# Level_Shifters.net
KiCad netlist of a schematic drawn in Altium Designer
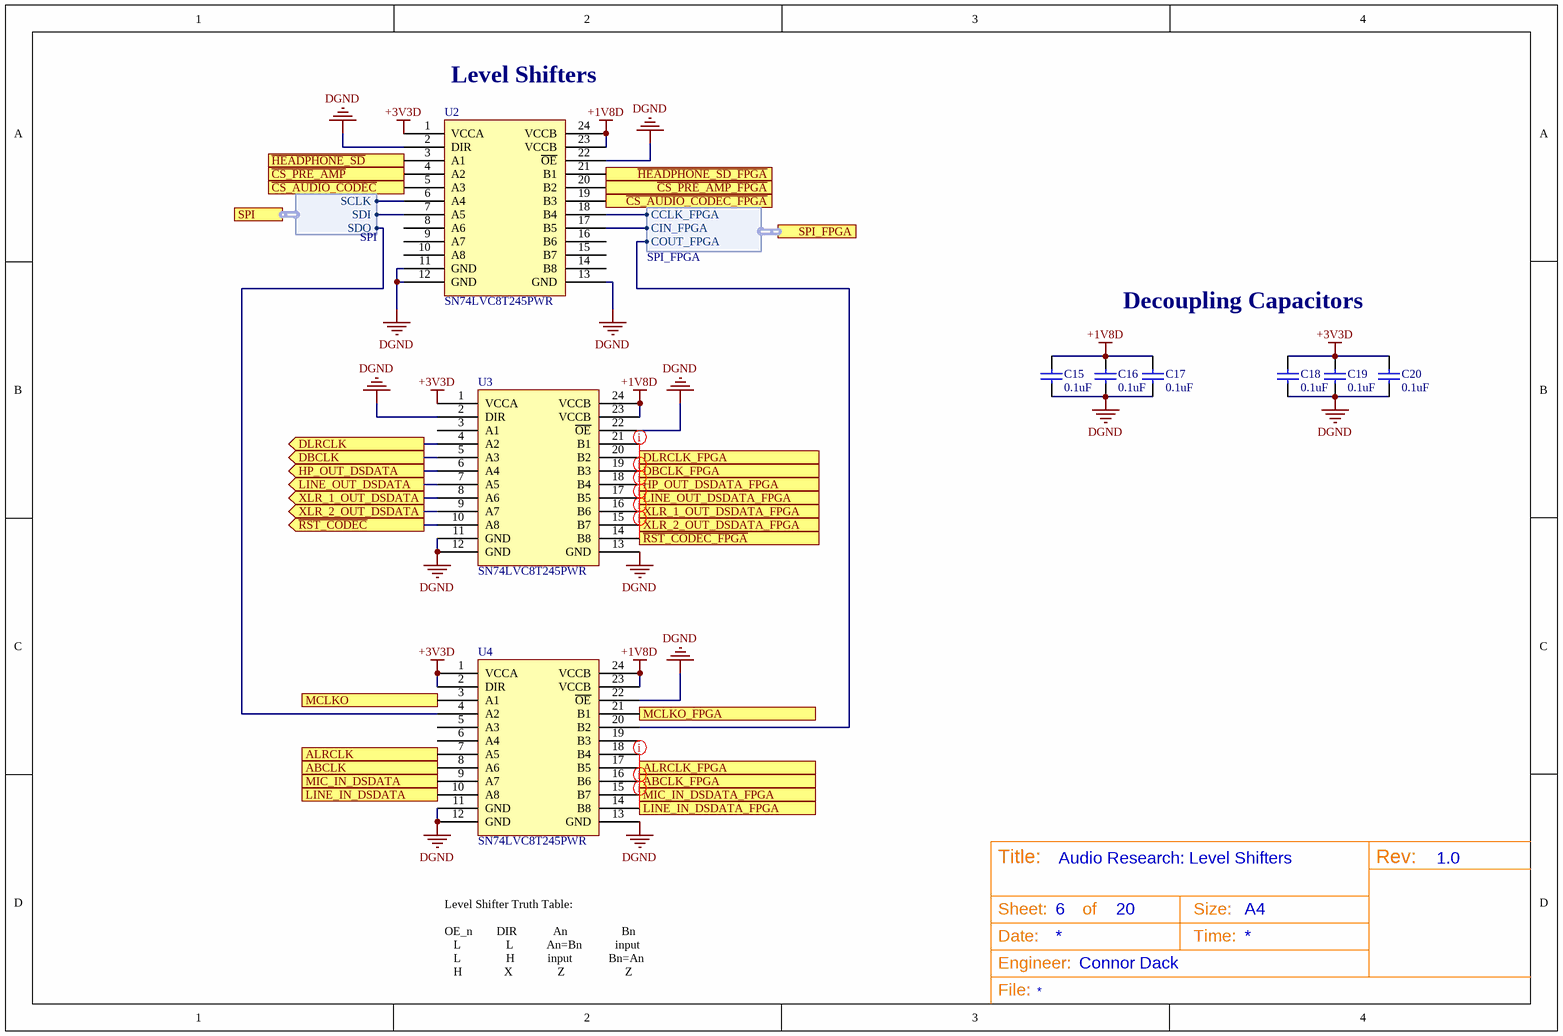
[diagram p0: Level_Shifters.SchDoc]

(export (version "E")
  (design (tool "Eeschema 10.0.6"))
  (components
    (comp (ref "C15")
      (value "CL10F104ZO8NNNC")
      (footprint "3-0603_L")
      (description "CAP CER 0.1UF 16V Y5V 0603")
      (fields
        (field (name "MANUFACTURER") "Samsung")
        (field (name "TOLERANCE") "80%")
        (field (name "CAPACITANCE") "0.1uF")
      )
      (libsource (lib "Schematic_Components_CD") (part "CL10F104ZO8NNNC"))
    )
    (comp (ref "C16")
      (value "CL10F104ZO8NNNC")
      (footprint "3-0603_L")
      (description "CAP CER 0.1UF 16V Y5V 0603")
      (fields
        (field (name "MANUFACTURER") "Samsung")
        (field (name "TOLERANCE") "80%")
        (field (name "CAPACITANCE") "0.1uF")
      )
      (libsource (lib "Schematic_Components_CD") (part "CL10F104ZO8NNNC"))
    )
    (comp (ref "C17")
      (value "CL10F104ZO8NNNC")
      (footprint "3-0603_L")
      (description "CAP CER 0.1UF 16V Y5V 0603")
      (fields
        (field (name "MANUFACTURER") "Samsung")
        (field (name "TOLERANCE") "80%")
        (field (name "CAPACITANCE") "0.1uF")
      )
      (libsource (lib "Schematic_Components_CD") (part "CL10F104ZO8NNNC"))
    )
    (comp (ref "C18")
      (value "CL10F104ZO8NNNC")
      (footprint "3-0603_L")
      (description "CAP CER 0.1UF 16V Y5V 0603")
      (fields
        (field (name "MANUFACTURER") "Samsung")
        (field (name "TOLERANCE") "80%")
        (field (name "CAPACITANCE") "0.1uF")
      )
      (libsource (lib "Schematic_Components_CD") (part "CL10F104ZO8NNNC"))
    )
    (comp (ref "C19")
      (value "CL10F104ZO8NNNC")
      (footprint "3-0603_L")
      (description "CAP CER 0.1UF 16V Y5V 0603")
      (fields
        (field (name "MANUFACTURER") "Samsung")
        (field (name "TOLERANCE") "80%")
        (field (name "CAPACITANCE") "0.1uF")
      )
      (libsource (lib "Schematic_Components_CD") (part "CL10F104ZO8NNNC"))
    )
    (comp (ref "C20")
      (value "CL10F104ZO8NNNC")
      (footprint "3-0603_L")
      (description "CAP CER 0.1UF 16V Y5V 0603")
      (fields
        (field (name "MANUFACTURER") "Samsung")
        (field (name "TOLERANCE") "80%")
        (field (name "CAPACITANCE") "0.1uF")
      )
      (libsource (lib "Schematic_Components_CD") (part "CL10F104ZO8NNNC"))
    )
    (comp (ref "U2")
      (value "IC BUS TRANSCVR 8BIT 24TSSOP")
      (footprint "TSOP65P640X120-24N")
      (description "Voltage Level Translator Bidirectional 1 Circuit 8 Channel 24-TSSOP")
      (fields
        (field (name "MANUFACTURER") "Texas Instruments")
        (field (name "MANUFACTURER PART NUMBER") "SN74LVC8T245PWR")
      )
      (libsource (lib "Schematic_Components_CD") (part "SN74LVC8T245PWR"))
    )
    (comp (ref "U3")
      (value "IC BUS TRANSCVR 8BIT 24TSSOP")
      (footprint "TSOP65P640X120-24N")
      (description "Voltage Level Translator Bidirectional 1 Circuit 8 Channel 24-TSSOP")
      (fields
        (field (name "MANUFACTURER") "Texas Instruments")
        (field (name "MANUFACTURER PART NUMBER") "SN74LVC8T245PWR")
      )
      (libsource (lib "Schematic_Components_CD") (part "SN74LVC8T245PWR"))
    )
    (comp (ref "U4")
      (value "IC BUS TRANSCVR 8BIT 24TSSOP")
      (footprint "TSOP65P640X120-24N")
      (description "Voltage Level Translator Bidirectional 1 Circuit 8 Channel 24-TSSOP")
      (fields
        (field (name "MANUFACTURER") "Texas Instruments")
        (field (name "MANUFACTURER PART NUMBER") "SN74LVC8T245PWR")
      )
      (libsource (lib "Schematic_Components_CD") (part "SN74LVC8T245PWR"))
    )
  )
  (nets
    (net (code "3") (name "+1V8D") (class "Default")
      (node (ref "C15") (pin "1") (pinfunction "1_1") (pintype "passive"))
      (node (ref "C16") (pin "1") (pinfunction "1_1") (pintype "passive"))
      (node (ref "C17") (pin "1") (pinfunction "1_1") (pintype "passive"))
      (node (ref "U2") (pin "23") (pinfunction "VCCB_23") (pintype "power_in"))
      (node (ref "U2") (pin "24") (pinfunction "VCCB_24") (pintype "power_in"))
      (node (ref "U3") (pin "23") (pinfunction "VCCB_23") (pintype "power_in"))
      (node (ref "U3") (pin "24") (pinfunction "VCCB_24") (pintype "power_in"))
      (node (ref "U4") (pin "23") (pinfunction "VCCB_23") (pintype "power_in"))
      (node (ref "U4") (pin "24") (pinfunction "VCCB_24") (pintype "power_in"))
    )
    (net (code "4") (name "+3V3D") (class "Default")
      (node (ref "C18") (pin "1") (pinfunction "1_1") (pintype "passive"))
      (node (ref "C19") (pin "1") (pinfunction "1_1") (pintype "passive"))
      (node (ref "C20") (pin "1") (pinfunction "1_1") (pintype "passive"))
      (node (ref "U2") (pin "1") (pinfunction "VCCA_1") (pintype "power_in"))
      (node (ref "U3") (pin "1") (pinfunction "VCCA_1") (pintype "power_in"))
      (node (ref "U4") (pin "1") (pinfunction "VCCA_1") (pintype "power_in"))
      (node (ref "U4") (pin "2") (pinfunction "DIR_2") (pintype "passive"))
    )
    (net (code "5") (name "/ABCLK") (class "Default")
      (node (ref "U4") (pin "8") (pinfunction "A6_8") (pintype "passive"))
    )
    (net (code "6") (name "/ABCLK_FPGA") (class "Default")
      (node (ref "U4") (pin "16") (pinfunction "B6_16") (pintype "passive"))
    )
    (net (code "7") (name "/ALRCLK") (class "Default")
      (node (ref "U4") (pin "7") (pinfunction "A5_7") (pintype "passive"))
    )
    (net (code "8") (name "/ALRCLK_FPGA") (class "Default")
      (node (ref "U4") (pin "17") (pinfunction "B5_17") (pintype "passive"))
    )
    (net (code "9") (name "/CCLK_FPGA") (class "Default")
      (node (ref "U2") (pin "18") (pinfunction "B4_18") (pintype "passive"))
    )
    (net (code "10") (name "/CIN_FPGA") (class "Default")
      (node (ref "U2") (pin "17") (pinfunction "B5_17") (pintype "passive"))
    )
    (net (code "11") (name "/COUT_FPGA") (class "Default")
      (node (ref "U4") (pin "20") (pinfunction "B2_20") (pintype "passive"))
    )
    (net (code "12") (name "/DBCLK") (class "Default")
      (node (ref "U3") (pin "5") (pinfunction "A3_5") (pintype "passive"))
    )
    (net (code "13") (name "/DBCLK_FPGA") (class "Default")
      (node (ref "U3") (pin "19") (pinfunction "B3_19") (pintype "passive"))
    )
    (net (code "14") (name "/DLRCLK") (class "Default")
      (node (ref "U3") (pin "4") (pinfunction "A2_4") (pintype "passive"))
    )
    (net (code "15") (name "/DLRCLK_FPGA") (class "Default")
      (node (ref "U3") (pin "20") (pinfunction "B2_20") (pintype "passive"))
    )
    (net (code "16") (name "/HP_OUT_DSDATA") (class "Default")
      (node (ref "U3") (pin "6") (pinfunction "A4_6") (pintype "passive"))
    )
    (net (code "17") (name "/HP_OUT_DSDATA_FPGA") (class "Default")
      (node (ref "U3") (pin "18") (pinfunction "B4_18") (pintype "passive"))
    )
    (net (code "18") (name "/LINE_IN_DSDATA") (class "Default")
      (node (ref "U4") (pin "10") (pinfunction "A8_10") (pintype "passive"))
    )
    (net (code "19") (name "/LINE_IN_DSDATA_FPGA") (class "Default")
      (node (ref "U4") (pin "14") (pinfunction "B8_14") (pintype "passive"))
    )
    (net (code "20") (name "/LINE_OUT_DSDATA") (class "Default")
      (node (ref "U3") (pin "7") (pinfunction "A5_7") (pintype "passive"))
    )
    (net (code "21") (name "/LINE_OUT_DSDATA_FPGA") (class "Default")
      (node (ref "U3") (pin "17") (pinfunction "B5_17") (pintype "passive"))
    )
    (net (code "22") (name "/MCLKO") (class "Default")
      (node (ref "U4") (pin "3") (pinfunction "A1_3") (pintype "passive"))
    )
    (net (code "23") (name "/MCLKO_FPGA") (class "Default")
      (node (ref "U4") (pin "21") (pinfunction "B1_21") (pintype "passive"))
    )
    (net (code "24") (name "/MIC_IN_DSDATA") (class "Default")
      (node (ref "U4") (pin "9") (pinfunction "A7_9") (pintype "passive"))
    )
    (net (code "25") (name "/MIC_IN_DSDATA_FPGA") (class "Default")
      (node (ref "U4") (pin "15") (pinfunction "B7_15") (pintype "passive"))
    )
    (net (code "26") (name "/SCLK") (class "Default")
      (node (ref "U2") (pin "6") (pinfunction "A4_6") (pintype "passive"))
    )
    (net (code "27") (name "/SDI") (class "Default")
      (node (ref "U2") (pin "7") (pinfunction "A5_7") (pintype "passive"))
    )
    (net (code "28") (name "/SDO") (class "Default")
      (node (ref "U4") (pin "4") (pinfunction "A2_4") (pintype "passive"))
    )
    (net (code "29") (name "/XLR_1_OUT_DSDATA") (class "Default")
      (node (ref "U3") (pin "8") (pinfunction "A6_8") (pintype "passive"))
    )
    (net (code "30") (name "/XLR_1_OUT_DSDATA_FPGA") (class "Default")
      (node (ref "U3") (pin "16") (pinfunction "B6_16") (pintype "passive"))
    )
    (net (code "31") (name "/XLR_2_OUT_DSDATA") (class "Default")
      (node (ref "U3") (pin "9") (pinfunction "A7_9") (pintype "passive"))
    )
    (net (code "32") (name "/XLR_2_OUT_DSDATA_FPGA") (class "Default")
      (node (ref "U3") (pin "15") (pinfunction "B7_15") (pintype "passive"))
    )
    (net (code "35") (name "/~{CS_AUDIO_CODEC_FPGA}") (class "Default")
      (node (ref "U2") (pin "19") (pinfunction "B3_19") (pintype "passive"))
    )
    (net (code "36") (name "/~{CS_AUDIO_CODEC}") (class "Default")
      (node (ref "U2") (pin "5") (pinfunction "A3_5") (pintype "passive"))
    )
    (net (code "37") (name "/~{CS_PRE_AMP_FPGA}") (class "Default")
      (node (ref "U2") (pin "20") (pinfunction "B2_20") (pintype "passive"))
    )
    (net (code "38") (name "/~{CS_PRE_AMP}") (class "Default")
      (node (ref "U2") (pin "4") (pinfunction "A2_4") (pintype "passive"))
    )
    (net (code "39") (name "/~{HEADPHONE_SD_FPGA}") (class "Default")
      (node (ref "U2") (pin "21") (pinfunction "B1_21") (pintype "passive"))
    )
    (net (code "40") (name "/~{HEADPHONE_SD}") (class "Default")
      (node (ref "U2") (pin "3") (pinfunction "A1_3") (pintype "passive"))
    )
    (net (code "41") (name "/~{RST_CODEC_FPGA}") (class "Default")
      (node (ref "U3") (pin "14") (pinfunction "B8_14") (pintype "passive"))
    )
    (net (code "42") (name "/~{RST_CODEC}") (class "Default")
      (node (ref "U3") (pin "10") (pinfunction "A8_10") (pintype "passive"))
    )
    (net (code "43") (name "DGND") (class "Default")
      (node (ref "C15") (pin "2") (pinfunction "2_2") (pintype "passive"))
      (node (ref "C16") (pin "2") (pinfunction "2_2") (pintype "passive"))
      (node (ref "C17") (pin "2") (pinfunction "2_2") (pintype "passive"))
      (node (ref "C18") (pin "2") (pinfunction "2_2") (pintype "passive"))
      (node (ref "C19") (pin "2") (pinfunction "2_2") (pintype "passive"))
      (node (ref "C20") (pin "2") (pinfunction "2_2") (pintype "passive"))
      (node (ref "U2") (pin "11") (pinfunction "GND_11") (pintype "power_in"))
      (node (ref "U2") (pin "12") (pinfunction "GND_12") (pintype "power_in"))
      (node (ref "U2") (pin "13") (pinfunction "GND_13") (pintype "power_in"))
      (node (ref "U2") (pin "2") (pinfunction "DIR_2") (pintype "passive"))
      (node (ref "U2") (pin "22") (pinfunction "~{OE}_22") (pintype "passive"))
      (node (ref "U3") (pin "11") (pinfunction "GND_11") (pintype "power_in"))
      (node (ref "U3") (pin "12") (pinfunction "GND_12") (pintype "power_in"))
      (node (ref "U3") (pin "13") (pinfunction "GND_13") (pintype "power_in"))
      (node (ref "U3") (pin "2") (pinfunction "DIR_2") (pintype "passive"))
      (node (ref "U3") (pin "22") (pinfunction "~{OE}_22") (pintype "passive"))
      (node (ref "U4") (pin "11") (pinfunction "GND_11") (pintype "power_in"))
      (node (ref "U4") (pin "12") (pinfunction "GND_12") (pintype "power_in"))
      (node (ref "U4") (pin "13") (pinfunction "GND_13") (pintype "power_in"))
      (node (ref "U4") (pin "22") (pinfunction "~{OE}_22") (pintype "passive"))
    )
    (net (code "44") (name "unconnected-(U2-A6-Pad8)") (class "Default")
      (node (ref "U2") (pin "8") (pinfunction "A6_8") (pintype "passive"))
    )
    (net (code "45") (name "unconnected-(U2-A7-Pad9)") (class "Default")
      (node (ref "U2") (pin "9") (pinfunction "A7_9") (pintype "passive"))
    )
    (net (code "46") (name "unconnected-(U2-A8-Pad10)") (class "Default")
      (node (ref "U2") (pin "10") (pinfunction "A8_10") (pintype "passive"))
    )
    (net (code "47") (name "unconnected-(U2-B6-Pad16)") (class "Default")
      (node (ref "U2") (pin "16") (pinfunction "B6_16") (pintype "passive"))
    )
    (net (code "48") (name "unconnected-(U2-B7-Pad15)") (class "Default")
      (node (ref "U2") (pin "15") (pinfunction "B7_15") (pintype "passive"))
    )
    (net (code "49") (name "unconnected-(U2-B8-Pad14)") (class "Default")
      (node (ref "U2") (pin "14") (pinfunction "B8_14") (pintype "passive"))
    )
    (net (code "50") (name "unconnected-(U3-A1-Pad3)") (class "Default")
      (node (ref "U3") (pin "3") (pinfunction "A1_3") (pintype "passive"))
    )
    (net (code "51") (name "unconnected-(U3-B1-Pad21)") (class "Default")
      (node (ref "U3") (pin "21") (pinfunction "B1_21") (pintype "passive"))
    )
    (net (code "52") (name "unconnected-(U4-A3-Pad5)") (class "Default")
      (node (ref "U4") (pin "5") (pinfunction "A3_5") (pintype "passive"))
    )
    (net (code "53") (name "unconnected-(U4-A4-Pad6)") (class "Default")
      (node (ref "U4") (pin "6") (pinfunction "A4_6") (pintype "passive"))
    )
    (net (code "54") (name "unconnected-(U4-B3-Pad19)") (class "Default")
      (node (ref "U4") (pin "19") (pinfunction "B3_19") (pintype "passive"))
    )
    (net (code "55") (name "unconnected-(U4-B4-Pad18)") (class "Default")
      (node (ref "U4") (pin "18") (pinfunction "B4_18") (pintype "passive"))
    )
  )
)
